# EXCISS_SEU.net
KiCad netlist of a schematic drawn in EAGLE
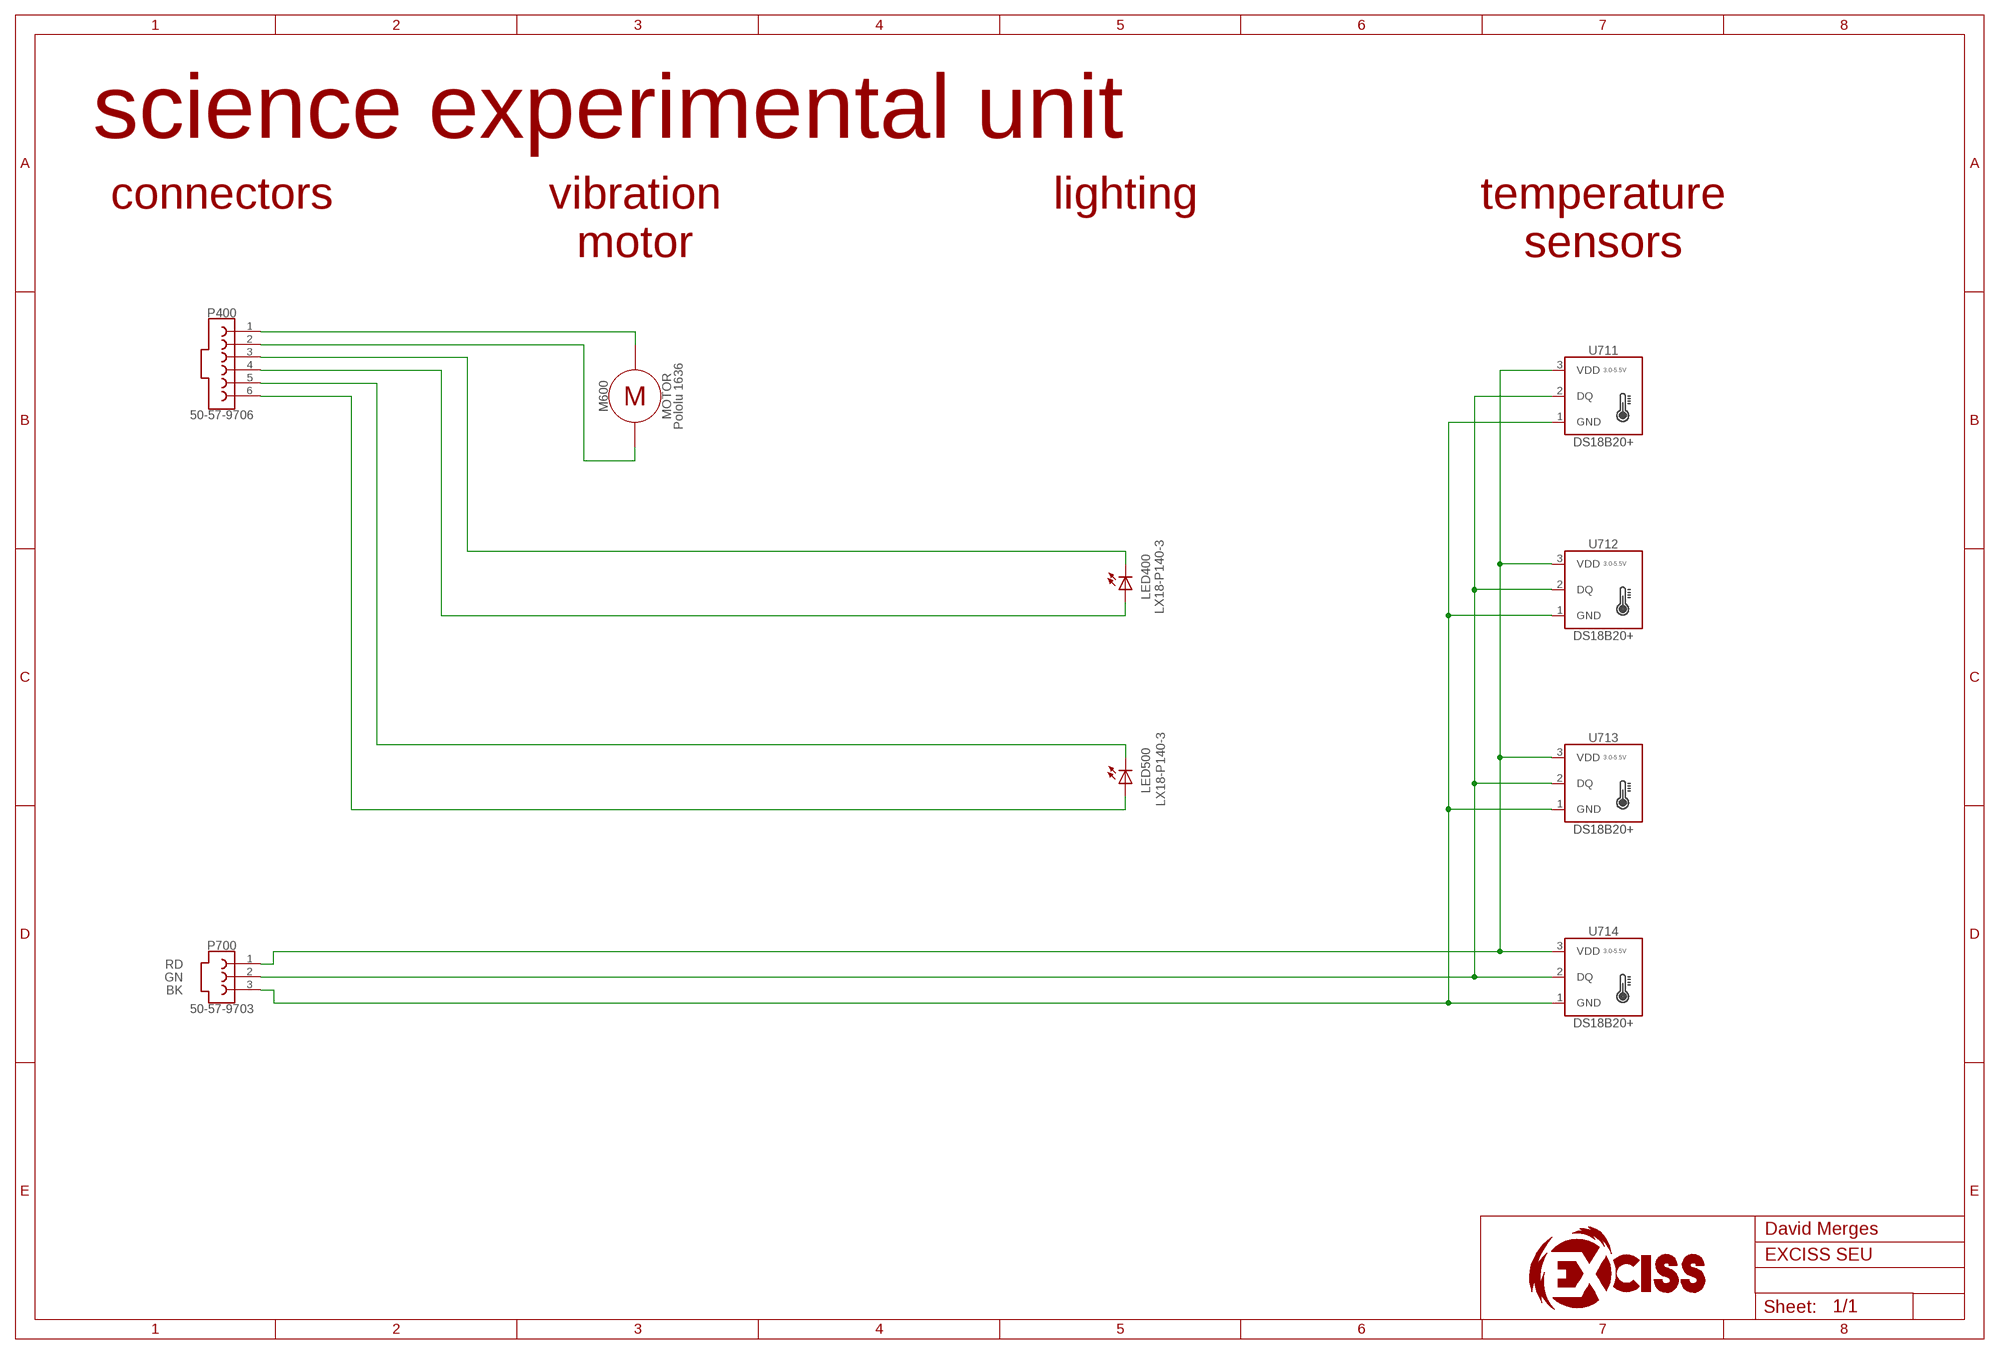
[diagram p0: schematic, sheet 1]

(export (version "E")
  (design (tool "Eeschema 10.0.6"))
  (components
    (comp (ref "LED400")
      (value "LX18-P140-3")
      (footprint "eagle-import:LED3MM")
      (libsource (lib "eagle-import") (part "LED3MM"))
    )
    (comp (ref "LED500")
      (value "LX18-P140-3")
      (footprint "eagle-import:LED3MM")
      (libsource (lib "eagle-import") (part "LED3MM"))
    )
    (comp (ref "M600")
      (value "MOTOR")
      (footprint "eagle-import:DUMMY")
      (libsource (lib "eagle-import") (part "MOTOR"))
    )
    (comp (ref "P400")
      (value "50-57-9706")
      (footprint "eagle-import:DUMMY")
      (libsource (lib "eagle-import") (part "14-56-2064"))
    )
    (comp (ref "P700")
      (value "50-57-9703")
      (footprint "eagle-import:DUMMY")
      (libsource (lib "eagle-import") (part "14-56-2034"))
    )
    (comp (ref "U711")
      (value "DS18B20+")
      (footprint "eagle-import:TO-92-STRAIGHT")
      (libsource (lib "eagle-import") (part "DS18B20+"))
    )
    (comp (ref "U712")
      (value "DS18B20+")
      (footprint "eagle-import:TO-92-STRAIGHT")
      (libsource (lib "eagle-import") (part "DS18B20+"))
    )
    (comp (ref "U713")
      (value "DS18B20+")
      (footprint "eagle-import:TO-92-STRAIGHT")
      (libsource (lib "eagle-import") (part "DS18B20+"))
    )
    (comp (ref "U714")
      (value "DS18B20+")
      (footprint "eagle-import:TO-92-STRAIGHT")
      (libsource (lib "eagle-import") (part "DS18B20+"))
    )
  )
  (nets
    (net (code "1") (name "Net-(LED400-C)") (class "Default")
      (node (ref "LED400") (pin "K") (pinfunction "C_K") (pintype "passive"))
      (node (ref "P400") (pin "3") (pinfunction "3_3") (pintype "passive"))
    )
    (net (code "2") (name "Net-(LED400-PadA)") (class "Default")
      (node (ref "LED400") (pin "A") (pinfunction "A_A") (pintype "passive"))
      (node (ref "P400") (pin "4") (pinfunction "4_4") (pintype "passive"))
    )
    (net (code "3") (name "Net-(LED500-C)") (class "Default")
      (node (ref "LED500") (pin "K") (pinfunction "C_K") (pintype "passive"))
      (node (ref "P400") (pin "5") (pinfunction "5_5") (pintype "passive"))
    )
    (net (code "4") (name "Net-(LED500-PadA)") (class "Default")
      (node (ref "LED500") (pin "A") (pinfunction "A_A") (pintype "passive"))
      (node (ref "P400") (pin "6") (pinfunction "6_6") (pintype "passive"))
    )
    (net (code "5") (name "Net-(M600-P$1)") (class "Default")
      (node (ref "M600") (pin "1") (pinfunction "P$1_1") (pintype "bidirectional"))
      (node (ref "P400") (pin "1") (pinfunction "1_1") (pintype "passive"))
    )
    (net (code "6") (name "Net-(M600-P$2)") (class "Default")
      (node (ref "M600") (pin "2") (pinfunction "P$2_2") (pintype "bidirectional"))
      (node (ref "P400") (pin "2") (pinfunction "2_2") (pintype "passive"))
    )
    (net (code "7") (name "Net-(U711-DQ)") (class "Default")
      (node (ref "P700") (pin "2") (pinfunction "2_2") (pintype "passive"))
      (node (ref "U711") (pin "2") (pinfunction "DQ_2") (pintype "bidirectional"))
      (node (ref "U712") (pin "2") (pinfunction "DQ_2") (pintype "bidirectional"))
      (node (ref "U713") (pin "2") (pinfunction "DQ_2") (pintype "bidirectional"))
      (node (ref "U714") (pin "2") (pinfunction "DQ_2") (pintype "bidirectional"))
    )
    (net (code "8") (name "Net-(U711-GND)") (class "Default")
      (node (ref "P700") (pin "3") (pinfunction "3_3") (pintype "passive"))
      (node (ref "U711") (pin "1") (pinfunction "GND_1") (pintype "power_in"))
      (node (ref "U712") (pin "1") (pinfunction "GND_1") (pintype "power_in"))
      (node (ref "U713") (pin "1") (pinfunction "GND_1") (pintype "power_in"))
      (node (ref "U714") (pin "1") (pinfunction "GND_1") (pintype "power_in"))
    )
    (net (code "9") (name "Net-(U711-VDD)") (class "Default")
      (node (ref "P700") (pin "1") (pinfunction "1_1") (pintype "passive"))
      (node (ref "U711") (pin "3") (pinfunction "VDD_3") (pintype "power_in"))
      (node (ref "U712") (pin "3") (pinfunction "VDD_3") (pintype "power_in"))
      (node (ref "U713") (pin "3") (pinfunction "VDD_3") (pintype "power_in"))
      (node (ref "U714") (pin "3") (pinfunction "VDD_3") (pintype "power_in"))
    )
  )
)
